# CP2102.net
KiCad netlist of a schematic drawn in Altium Designer
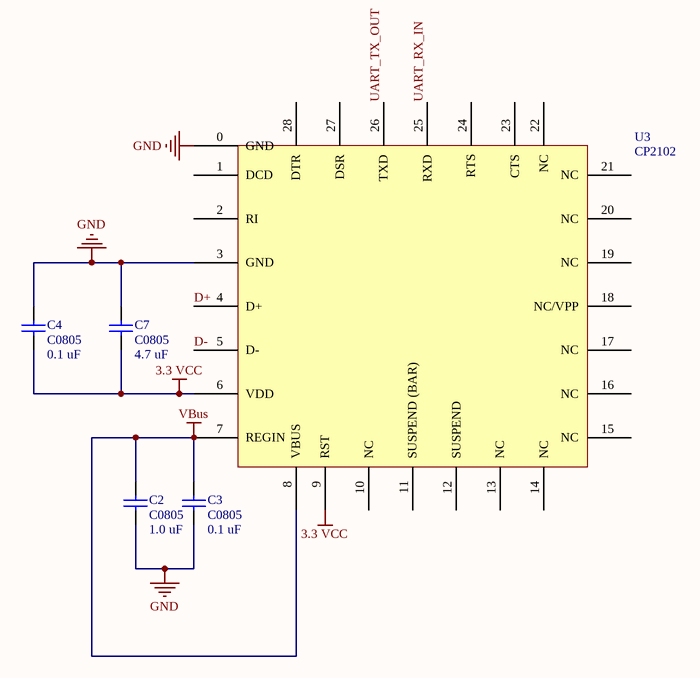
[diagram p0: CP2102.SchDoc]

(export (version "E")
  (design (tool "Eeschema 10.0.6"))
  (components
    (comp (ref "C2")
      (value "C0805")
      (footprint "0805")
      (description "Ceramic Chip Capacitor - Standard")
      (fields (field (name "ALTIUM_VALUE") "1.0 uF") (field (name "PUBLISHER") "Altium Limited"))
      (libsource (lib "KEMET Chip Capacitor") (part "C0805"))
    )
    (comp (ref "C3")
      (value "C0805")
      (footprint "0805")
      (description "Ceramic Chip Capacitor - Standard")
      (fields (field (name "ALTIUM_VALUE") "0.1 uF") (field (name "PUBLISHER") "Altium Limited"))
      (libsource (lib "KEMET Chip Capacitor") (part "C0805"))
    )
    (comp (ref "C4")
      (value "C0805")
      (footprint "0805")
      (description "Ceramic Chip Capacitor - Standard")
      (fields (field (name "ALTIUM_VALUE") "0.1 uF") (field (name "PUBLISHER") "Altium Limited"))
      (libsource (lib "KEMET Chip Capacitor") (part "C0805"))
    )
    (comp (ref "C7")
      (value "C0805")
      (footprint "0805")
      (description "Ceramic Chip Capacitor - Standard")
      (fields (field (name "ALTIUM_VALUE") "4.7 uF") (field (name "PUBLISHER") "Altium Limited"))
      (libsource (lib "KEMET Chip Capacitor") (part "C0805"))
    )
    (comp (ref "U3") (value "CP2102") (footprint "CP2102") (libsource (lib "CP2012") (part "CP2102")))
  )
  (nets
    (net (code "1") (name "/D+") (class "Default")
      (node (ref "U3") (pin "4") (pinfunction "D+_4") (pintype "passive"))
    )
    (net (code "2") (name "/D-") (class "Default")
      (node (ref "U3") (pin "5") (pinfunction "D-_5") (pintype "passive"))
    )
    (net (code "3") (name "/UART_RX_IN") (class "Default")
      (node (ref "U3") (pin "25") (pinfunction "RXD_25") (pintype "passive"))
    )
    (net (code "4") (name "/UART_TX_OUT") (class "Default")
      (node (ref "U3") (pin "26") (pinfunction "TXD_26") (pintype "passive"))
    )
    (net (code "5") (name "3.3 VCC") (class "Default")
      (node (ref "C4") (pin "2") (pinfunction "2_2") (pintype "passive"))
      (node (ref "C7") (pin "2") (pinfunction "2_2") (pintype "passive"))
      (node (ref "U3") (pin "6") (pinfunction "VDD_6") (pintype "passive"))
      (node (ref "U3") (pin "9") (pinfunction "RST_9") (pintype "passive"))
    )
    (net (code "6") (name "GND") (class "Default")
      (node (ref "C2") (pin "1") (pinfunction "1_1") (pintype "passive"))
      (node (ref "C3") (pin "1") (pinfunction "1_1") (pintype "passive"))
      (node (ref "C4") (pin "1") (pinfunction "1_1") (pintype "passive"))
      (node (ref "C7") (pin "1") (pinfunction "1_1") (pintype "passive"))
      (node (ref "U3") (pin "0") (pinfunction "GND_0") (pintype "passive"))
      (node (ref "U3") (pin "3") (pinfunction "GND_3") (pintype "passive"))
    )
    (net (code "7") (name "VBus") (class "Default")
      (node (ref "C2") (pin "2") (pinfunction "2_2") (pintype "passive"))
      (node (ref "C3") (pin "2") (pinfunction "2_2") (pintype "passive"))
      (node (ref "U3") (pin "7") (pinfunction "REGIN_7") (pintype "passive"))
      (node (ref "U3") (pin "8") (pinfunction "VBUS_8") (pintype "passive"))
    )
    (net (code "8") (name "unconnected-(U3-CTS-Pad23)") (class "Default")
      (node (ref "U3") (pin "23") (pinfunction "CTS_23") (pintype "passive"))
    )
    (net (code "9") (name "unconnected-(U3-DCD-Pad1)") (class "Default")
      (node (ref "U3") (pin "1") (pinfunction "DCD_1") (pintype "passive"))
    )
    (net (code "10") (name "unconnected-(U3-DSR-Pad27)") (class "Default")
      (node (ref "U3") (pin "27") (pinfunction "DSR_27") (pintype "passive"))
    )
    (net (code "11") (name "unconnected-(U3-DTR-Pad28)") (class "Default")
      (node (ref "U3") (pin "28") (pinfunction "DTR_28") (pintype "passive"))
    )
    (net (code "12") (name "unconnected-(U3-NC-Pad10)") (class "Default")
      (node (ref "U3") (pin "10") (pinfunction "NC_10") (pintype "passive"))
    )
    (net (code "13") (name "unconnected-(U3-NC-Pad13)") (class "Default")
      (node (ref "U3") (pin "13") (pinfunction "NC_13") (pintype "passive"))
    )
    (net (code "14") (name "unconnected-(U3-NC-Pad14)") (class "Default")
      (node (ref "U3") (pin "14") (pinfunction "NC_14") (pintype "passive"))
    )
    (net (code "15") (name "unconnected-(U3-NC-Pad15)") (class "Default")
      (node (ref "U3") (pin "15") (pinfunction "NC_15") (pintype "passive"))
    )
    (net (code "16") (name "unconnected-(U3-NC-Pad16)") (class "Default")
      (node (ref "U3") (pin "16") (pinfunction "NC_16") (pintype "passive"))
    )
    (net (code "17") (name "unconnected-(U3-NC-Pad17)") (class "Default")
      (node (ref "U3") (pin "17") (pinfunction "NC_17") (pintype "passive"))
    )
    (net (code "18") (name "unconnected-(U3-NC-Pad19)") (class "Default")
      (node (ref "U3") (pin "19") (pinfunction "NC_19") (pintype "passive"))
    )
    (net (code "19") (name "unconnected-(U3-NC-Pad20)") (class "Default")
      (node (ref "U3") (pin "20") (pinfunction "NC_20") (pintype "passive"))
    )
    (net (code "20") (name "unconnected-(U3-NC-Pad21)") (class "Default")
      (node (ref "U3") (pin "21") (pinfunction "NC_21") (pintype "passive"))
    )
    (net (code "21") (name "unconnected-(U3-NC-Pad22)") (class "Default")
      (node (ref "U3") (pin "22") (pinfunction "NC_22") (pintype "passive"))
    )
    (net (code "22") (name "unconnected-(U3-NC{slash}VPP-Pad18)") (class "Default")
      (node (ref "U3") (pin "18") (pinfunction "NC/VPP_18") (pintype "passive"))
    )
    (net (code "23") (name "unconnected-(U3-RI-Pad2)") (class "Default")
      (node (ref "U3") (pin "2") (pinfunction "RI_2") (pintype "passive"))
    )
    (net (code "24") (name "unconnected-(U3-RTS-Pad24)") (class "Default")
      (node (ref "U3") (pin "24") (pinfunction "RTS_24") (pintype "passive"))
    )
    (net (code "25") (name "unconnected-(U3-SUSPEND-Pad12)") (class "Default")
      (node (ref "U3") (pin "12") (pinfunction "SUSPEND_12") (pintype "passive"))
    )
    (net (code "26") (name "unconnected-(U3-SUSPEND_(BAR)-Pad11)") (class "Default")
      (node (ref "U3") (pin "11") (pinfunction "SUSPEND_(BAR)_11") (pintype "passive"))
    )
  )
)
